# UJA1169.net
KiCad netlist of a schematic drawn in Altium Designer
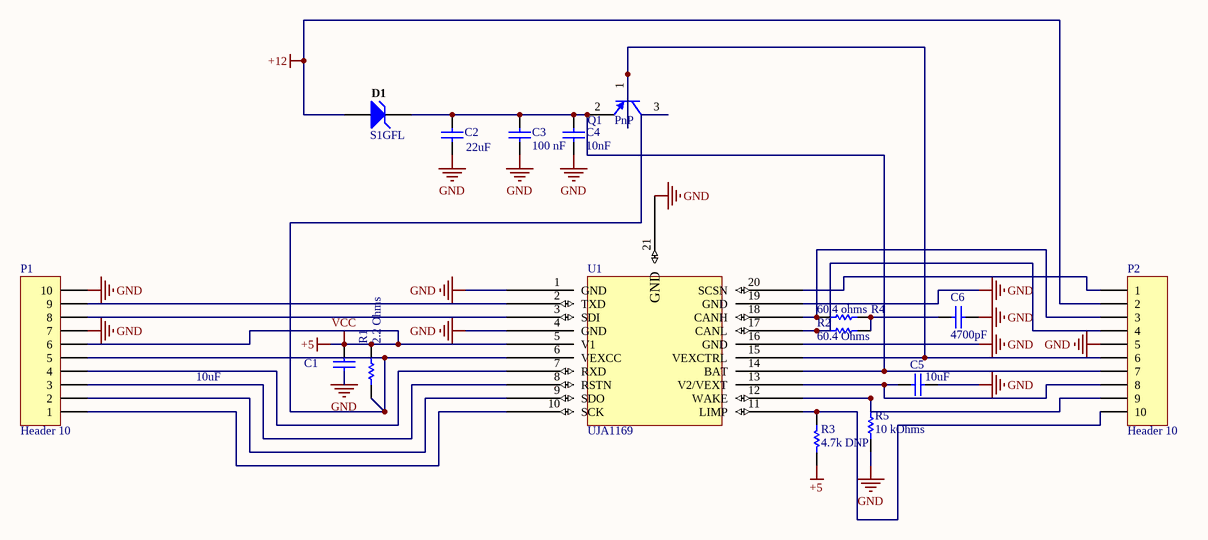
[diagram p0: UJA1169.SchDoc]

(export (version "E")
  (design (tool "Eeschema 10.0.6"))
  (components
    (comp (ref "C1")
      (value "10uF")
      (footprint "CAPC1206(3216)130_L")
      (description "C1206X106K8RACAUTO & JMK316BJ106KLHT - Thickness 10V -20% to +80% 1206 SMD")
      (fields (field (name "TOLERANCE") "-20% to +80%"))
      (libsource (lib "Altium Content Vault") (part "CAP"))
    )
    (comp (ref "C2")
      (value "22uF")
      (footprint "CAPC1210(3225)220_M")
      (description "GCJ32ER71C226KE01L - CAP 22uF 25V -20% to +80% 1210 (3225 Metric) Thickness 2.2mm SMD")
      (fields (field (name "TOLERANCE") "-20% to +80%"))
      (libsource (lib "Altium Content Vault") (part "CAP"))
    )
    (comp (ref "C3")
      (value "100 nF")
      (footprint "CAPC1005X55X10LL05")
      (description "AC0402KRX7R6BB104 - Multilayer Ceramic Capacitors MLCC - SMD/SMT 100 nF 10% 10V AEC-Q200")
      (fields (field (name "TOLERANCE") "±5%") (field (name "MANUFACTURER") "TDK"))
      (libsource (lib "Altium Content Vault") (part "CAP-NP-2"))
    )
    (comp (ref "C4")
      (value "10nF")
      (footprint "CAPC1005X55X25NL05T05")
      (description "AC0402KRX7R8BB103 - 10000PF 25V X7R 0402")
      (fields (field (name "MANUFACTURER") "Kemet") (field (name "PART NUMBER") "CBR04C100J5GAC"))
      (libsource (lib "Altium Content Vault") (part "CAP"))
    )
    (comp (ref "C5")
      (value "10uF")
      (footprint "CAPC1206(3216)130_L")
      (description "C1206X106K8RACAUTO - Thickness 10V -20% to +80% 1206 SMD")
      (fields (field (name "TOLERANCE") "-20% to +80%"))
      (libsource (lib "Altium Content Vault") (part "CAP"))
    )
    (comp (ref "C6")
      (value "4700pF")
      (footprint "CAPC1005X55X25NL05T05")
      (description "0402YC472K4T4A")
      (fields (field (name "MANUFACTURER") "Kemet") (field (name "PART NUMBER") "CBR04C100J5GAC"))
      (libsource (lib "Altium Content Vault") (part "CAP"))
    )
    (comp (ref "D1")
      (value "S1GFL")
      (footprint "VISH-SOD-123-2_V")
      (description "S1GFL - Diode")
      (fields (field (name "TOLERANCE") "+/- 5%") (field (name "MANUFACTURER") "Vishay Semiconductor"))
      (libsource (lib "Altium Content Vault") (part "VISH-DZEN_A1K2-2"))
    )
    (comp (ref "P1")
      (value "Header 10")
      (footprint "HDR1X10")
      (description "Header, 10-Pin")
      (fields (field (name "PUBLISHER") "Altium Limited"))
      (libsource (lib "") (part "Header 10_1"))
    )
    (comp (ref "P2")
      (value "Header 10")
      (footprint "HDR1X10")
      (description "Header, 10-Pin")
      (fields (field (name "PUBLISHER") "Altium Limited"))
      (libsource (lib "Miscellaneous Connectors") (part "Header 10"))
    )
    (comp (ref "Q1")
      (value "PnP")
      (footprint "ONSC-SOT-23-3-318-08_V")
      (description "NSV1C200LT1G - 100 V, 3 A, Low VCE(sat), PNP Transistor, 3-Pin SOT-23, Pb-Free, Tape and Reel")
      (fields (field (name "MANUFACTURER") "On Semiconductor") (field (name "PARTNUMBER") "NSV1C200LT1G"))
      (libsource (lib "Altium Content Vault") (part "ONSC-PNP-B1E2C3-3"))
    )
    (comp (ref "R1")
      (value "2.2 Ohms")
      (footprint "RESC1005X40X25LL10T10")
      (description "SG73P1ETTP2R20F")
      (fields (field (name "MANUFACTURER") "KOA Speer"))
      (libsource (lib "Altium Content Vault") (part "RES"))
    )
    (comp (ref "R2")
      (value "60.4 Ohms")
      (footprint "RESC1005X40X25LL05T05")
      (description "ERJ-2RKF60R4X")
      (fields (field (name "MANUFACTURER") "Panasonic"))
      (libsource (lib "Altium Content Vault") (part "RES"))
    )
    (comp (ref "R3")
      (value "4.7k DNP")
      (footprint "RESC1005X40X25LL05T05")
      (description "RK73H1ERTTP4701F")
      (fields (field (name "PART NUMBER") "CRCW0402432RFKTD") (field (name "MANUFACTURER") "Vishay Dale"))
      (libsource (lib "Altium Content Vault") (part "RES"))
    )
    (comp (ref "R4")
      (value "60.4 ohms")
      (footprint "RESC1005X40X25LL05T05")
      (description "ERJ-2RKF60R4X")
      (fields (field (name "MANUFACTURER") "Panasonic"))
      (libsource (lib "Altium Content Vault") (part "RES"))
    )
    (comp (ref "R5")
      (value "10 kOhms")
      (footprint "RESC1005X40X20LL05T10")
      (description "RG1005P-103-D-T10")
      (fields (field (name "MANUFACTURER") "Susumu"))
      (libsource (lib "Altium Content Vault") (part "RES"))
    )
    (comp (ref "U1")
      (value "UJA1169")
      (footprint "UJA1169_IPCcompliant")
      (libsource (lib "UJA1169") (part "UJA1169"))
    )
  )
  (nets
    (net (code "1") (name "+5") (class "Default")
      (node (ref "C1") (pin "2") (pinfunction "2_2") (pintype "passive"))
      (node (ref "P1") (pin "6") (pinfunction "6_6") (pintype "passive"))
      (node (ref "R1") (pin "2") (pinfunction "2_2") (pintype "passive"))
      (node (ref "R3") (pin "2") (pinfunction "2_2") (pintype "passive"))
      (node (ref "U1") (pin "5") (pinfunction "V1_5") (pintype "power_in"))
    )
    (net (code "2") (name "+12") (class "Default")
      (node (ref "D1") (pin "1") (pinfunction "A_1") (pintype "passive"))
      (node (ref "P2") (pin "2") (pinfunction "2_2") (pintype "passive"))
    )
    (net (code "3") (name "GND") (class "Default")
      (node (ref "C1") (pin "1") (pinfunction "1_1") (pintype "passive"))
      (node (ref "C2") (pin "1") (pinfunction "1_1") (pintype "passive"))
      (node (ref "C3") (pin "2") (pinfunction "2_2") (pintype "passive"))
      (node (ref "C4") (pin "2") (pinfunction "2_2") (pintype "passive"))
      (node (ref "C5") (pin "2") (pinfunction "2_2") (pintype "passive"))
      (node (ref "C6") (pin "2") (pinfunction "2_2") (pintype "passive"))
      (node (ref "P1") (pin "10") (pinfunction "10_10") (pintype "passive"))
      (node (ref "P1") (pin "7") (pinfunction "7_7") (pintype "passive"))
      (node (ref "P2") (pin "5") (pinfunction "5_5") (pintype "passive"))
      (node (ref "R5") (pin "2") (pinfunction "2_2") (pintype "passive"))
      (node (ref "U1") (pin "1") (pinfunction "GND_1") (pintype "power_in"))
      (node (ref "U1") (pin "16") (pinfunction "GND_16") (pintype "power_in"))
      (node (ref "U1") (pin "19") (pinfunction "GND_19") (pintype "power_in"))
      (node (ref "U1") (pin "21") (pinfunction "GND_21") (pintype "bidirectional"))
      (node (ref "U1") (pin "4") (pinfunction "GND_4") (pintype "power_in"))
    )
    (net (code "4") (name "Net-(C6-Pad1)") (class "Default")
      (node (ref "C6") (pin "1") (pinfunction "1_1") (pintype "passive"))
      (node (ref "R2") (pin "2") (pinfunction "2_2") (pintype "passive"))
      (node (ref "R4") (pin "2") (pinfunction "2_2") (pintype "passive"))
    )
    (net (code "5") (name "Net-(D1-K)") (class "Default")
      (node (ref "C2") (pin "2") (pinfunction "2_2") (pintype "passive"))
      (node (ref "C3") (pin "1") (pinfunction "1_1") (pintype "passive"))
      (node (ref "C4") (pin "1") (pinfunction "1_1") (pintype "passive"))
      (node (ref "D1") (pin "2") (pinfunction "K_2") (pintype "passive"))
      (node (ref "P2") (pin "7") (pinfunction "7_7") (pintype "passive"))
      (node (ref "Q1") (pin "2") (pinfunction "E_2") (pintype "passive"))
      (node (ref "U1") (pin "14") (pinfunction "BAT_14") (pintype "power_in"))
    )
    (net (code "6") (name "Net-(Q1-B)") (class "Default")
      (node (ref "P2") (pin "6") (pinfunction "6_6") (pintype "passive"))
      (node (ref "Q1") (pin "1") (pinfunction "B_1") (pintype "passive"))
      (node (ref "U1") (pin "15") (pinfunction "VEXCTRL_15") (pintype "power_in"))
    )
    (net (code "7") (name "Net-(Q1-C)") (class "Default")
      (node (ref "P1") (pin "5") (pinfunction "5_5") (pintype "passive"))
      (node (ref "Q1") (pin "3") (pinfunction "C_3") (pintype "passive"))
      (node (ref "R1") (pin "1") (pinfunction "1_1") (pintype "passive"))
      (node (ref "U1") (pin "6") (pinfunction "VEXCC_6") (pintype "power_in"))
    )
    (net (code "8") (name "Net-(U1-CANH)") (class "Default")
      (node (ref "P2") (pin "3") (pinfunction "3_3") (pintype "passive"))
      (node (ref "R4") (pin "1") (pinfunction "1_1") (pintype "passive"))
      (node (ref "U1") (pin "18") (pinfunction "CANH_18") (pintype "bidirectional"))
    )
    (net (code "9") (name "Net-(U1-CANL)") (class "Default")
      (node (ref "P2") (pin "4") (pinfunction "4_4") (pintype "passive"))
      (node (ref "R2") (pin "1") (pinfunction "1_1") (pintype "passive"))
      (node (ref "U1") (pin "17") (pinfunction "CANL_17") (pintype "bidirectional"))
    )
    (net (code "10") (name "Net-(U1-LIMP)") (class "Default")
      (node (ref "P2") (pin "10") (pinfunction "10_10") (pintype "passive"))
      (node (ref "R3") (pin "1") (pinfunction "1_1") (pintype "passive"))
      (node (ref "U1") (pin "11") (pinfunction "LIMP_11") (pintype "bidirectional"))
    )
    (net (code "11") (name "Net-(U1-RSTN)") (class "Default")
      (node (ref "P1") (pin "3") (pinfunction "3_3") (pintype "passive"))
      (node (ref "U1") (pin "8") (pinfunction "RSTN_8") (pintype "bidirectional"))
    )
    (net (code "12") (name "Net-(U1-RXD)") (class "Default")
      (node (ref "P1") (pin "4") (pinfunction "4_4") (pintype "passive"))
      (node (ref "U1") (pin "7") (pinfunction "RXD_7") (pintype "bidirectional"))
    )
    (net (code "13") (name "Net-(U1-SCK)") (class "Default")
      (node (ref "P1") (pin "1") (pinfunction "1_1") (pintype "passive"))
      (node (ref "U1") (pin "10") (pinfunction "SCK_10") (pintype "bidirectional"))
    )
    (net (code "14") (name "Net-(U1-SCSN)") (class "Default")
      (node (ref "P2") (pin "1") (pinfunction "1_1") (pintype "passive"))
      (node (ref "U1") (pin "20") (pinfunction "SCSN_20") (pintype "bidirectional"))
    )
    (net (code "15") (name "Net-(U1-SDI)") (class "Default")
      (node (ref "P1") (pin "8") (pinfunction "8_8") (pintype "passive"))
      (node (ref "U1") (pin "3") (pinfunction "SDI_3") (pintype "bidirectional"))
    )
    (net (code "16") (name "Net-(U1-SDO)") (class "Default")
      (node (ref "P1") (pin "2") (pinfunction "2_2") (pintype "passive"))
      (node (ref "U1") (pin "9") (pinfunction "SDO_9") (pintype "bidirectional"))
    )
    (net (code "17") (name "Net-(U1-TXD)") (class "Default")
      (node (ref "P1") (pin "9") (pinfunction "9_9") (pintype "passive"))
      (node (ref "U1") (pin "2") (pinfunction "TXD_2") (pintype "bidirectional"))
    )
    (net (code "18") (name "Net-(U1-V2{slash}VEXT)") (class "Default")
      (node (ref "C5") (pin "1") (pinfunction "1_1") (pintype "passive"))
      (node (ref "P2") (pin "8") (pinfunction "8_8") (pintype "passive"))
      (node (ref "U1") (pin "13") (pinfunction "V2/VEXT_13") (pintype "power_in"))
    )
    (net (code "19") (name "Net-(U1-WAKE)") (class "Default")
      (node (ref "P2") (pin "9") (pinfunction "9_9") (pintype "passive"))
      (node (ref "R5") (pin "1") (pinfunction "1_1") (pintype "passive"))
      (node (ref "U1") (pin "12") (pinfunction "WAKE_12") (pintype "bidirectional"))
    )
  )
)
